# sematik.net
KiCad netlist of a schematic drawn in EAGLE
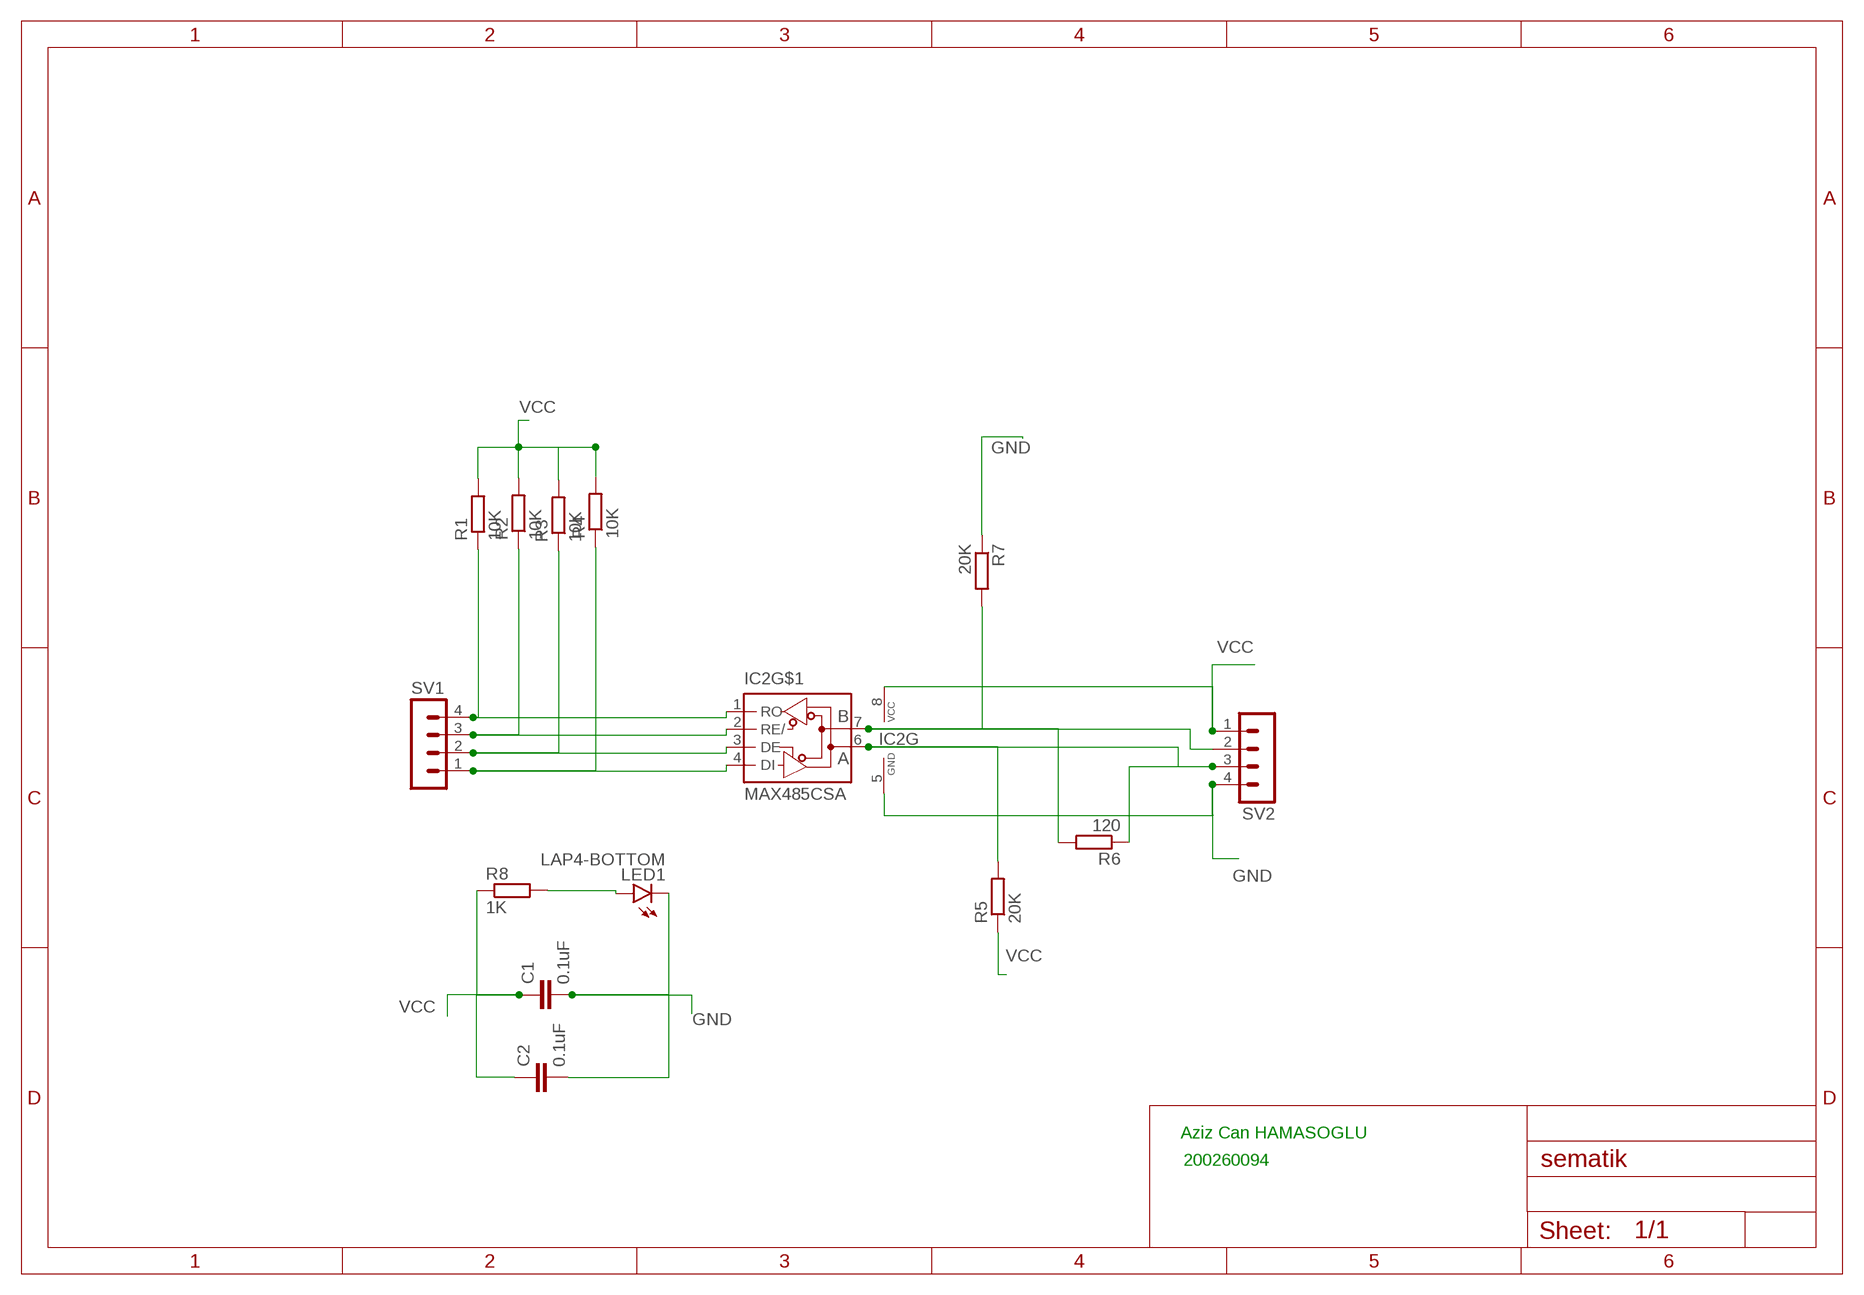
[diagram p0: schematic, sheet 1]

(export (version "E")
  (design (tool "Eeschema 10.0.6"))
  (components
    (comp (ref "C1")
      (value "0.1uF")
      (footprint "eagle-import:C0402K")
      (libsource (lib "eagle-import") (part "C-EUC0402K"))
    )
    (comp (ref "C2")
      (value "0.1uF")
      (footprint "eagle-import:C0402K")
      (libsource (lib "eagle-import") (part "C-EUC0402K"))
    )
    (comp (ref "IC2")
      (value "MAX485CSA")
      (footprint "eagle-import:SO08")
      (libsource (lib "eagle-import") (part "MAX485CSA"))
    )
    (comp (ref "LED1")
      (value "LAP4-BOTTOM")
      (footprint "eagle-import:P47F-BOTTOM")
      (libsource (lib "eagle-import") (part "P4-BOTTOMLA"))
    )
    (comp (ref "R1")
      (value "10K")
      (footprint "eagle-import:M1206")
      (libsource (lib "eagle-import") (part "R-EU_M1206"))
    )
    (comp (ref "R2")
      (value "10K")
      (footprint "eagle-import:M1206")
      (libsource (lib "eagle-import") (part "R-EU_M1206"))
    )
    (comp (ref "R3")
      (value "10K")
      (footprint "eagle-import:M1206")
      (libsource (lib "eagle-import") (part "R-EU_M1206"))
    )
    (comp (ref "R4")
      (value "10K")
      (footprint "eagle-import:M1206")
      (libsource (lib "eagle-import") (part "R-EU_M1206"))
    )
    (comp (ref "R5")
      (value "20K")
      (footprint "eagle-import:M1206")
      (libsource (lib "eagle-import") (part "R-EU_M1206"))
    )
    (comp (ref "R6")
      (value "120")
      (footprint "eagle-import:M1206")
      (libsource (lib "eagle-import") (part "R-EU_M1206"))
    )
    (comp (ref "R7")
      (value "20K")
      (footprint "eagle-import:M1206")
      (libsource (lib "eagle-import") (part "R-EU_M1206"))
    )
    (comp (ref "R8")
      (value "1K")
      (footprint "eagle-import:M1206")
      (libsource (lib "eagle-import") (part "R-EU_M1206"))
    )
    (comp (ref "SV1")
      (value "MA04-1")
      (footprint "eagle-import:MA04-1")
      (libsource (lib "eagle-import") (part "MA04-1"))
    )
    (comp (ref "SV2")
      (value "MA04-1")
      (footprint "eagle-import:MA04-1")
      (libsource (lib "eagle-import") (part "MA04-1"))
    )
  )
  (nets
    (net (code "1") (name "/GND") (class "Default")
      (node (ref "C1") (pin "2") (pinfunction "2_2") (pintype "passive"))
      (node (ref "C2") (pin "2") (pinfunction "2_2") (pintype "passive"))
      (node (ref "IC2") (pin "5") (pinfunction "GND_5") (pintype "power_in"))
      (node (ref "LED1") (pin "C") (pinfunction "C_C") (pintype "passive"))
      (node (ref "R7") (pin "1") (pinfunction "1_1") (pintype "passive"))
      (node (ref "SV2") (pin "4") (pinfunction "4_4") (pintype "passive"))
    )
    (net (code "2") (name "/VCC") (class "Default")
      (node (ref "C1") (pin "1") (pinfunction "1_1") (pintype "passive"))
      (node (ref "C2") (pin "1") (pinfunction "1_1") (pintype "passive"))
      (node (ref "IC2") (pin "8") (pinfunction "VCC_8") (pintype "power_in"))
      (node (ref "R1") (pin "2") (pinfunction "2_2") (pintype "passive"))
      (node (ref "R2") (pin "2") (pinfunction "2_2") (pintype "passive"))
      (node (ref "R3") (pin "2") (pinfunction "2_2") (pintype "passive"))
      (node (ref "R4") (pin "2") (pinfunction "2_2") (pintype "passive"))
      (node (ref "R5") (pin "1") (pinfunction "1_1") (pintype "passive"))
      (node (ref "R8") (pin "1") (pinfunction "1_1") (pintype "passive"))
      (node (ref "SV2") (pin "1") (pinfunction "1_1") (pintype "passive"))
    )
    (net (code "3") (name "Net-(IC2B-A)") (class "Default")
      (node (ref "IC2") (pin "6") (pinfunction "A_6") (pintype "passive"))
      (node (ref "R5") (pin "2") (pinfunction "2_2") (pintype "passive"))
      (node (ref "R6") (pin "1") (pinfunction "1_1") (pintype "passive"))
      (node (ref "SV2") (pin "3") (pinfunction "3_3") (pintype "passive"))
    )
    (net (code "4") (name "Net-(IC2B-B)") (class "Default")
      (node (ref "IC2") (pin "7") (pinfunction "B_7") (pintype "passive"))
      (node (ref "R6") (pin "2") (pinfunction "2_2") (pintype "passive"))
      (node (ref "R7") (pin "2") (pinfunction "2_2") (pintype "passive"))
      (node (ref "SV2") (pin "2") (pinfunction "2_2") (pintype "passive"))
    )
    (net (code "5") (name "Net-(IC2B-DE)") (class "Default")
      (node (ref "IC2") (pin "3") (pinfunction "DE_3") (pintype "input"))
      (node (ref "R3") (pin "1") (pinfunction "1_1") (pintype "passive"))
      (node (ref "SV1") (pin "2") (pinfunction "2_2") (pintype "passive"))
    )
    (net (code "6") (name "Net-(IC2B-DI)") (class "Default")
      (node (ref "IC2") (pin "4") (pinfunction "DI_4") (pintype "input"))
      (node (ref "R4") (pin "1") (pinfunction "1_1") (pintype "passive"))
      (node (ref "SV1") (pin "1") (pinfunction "1_1") (pintype "passive"))
    )
    (net (code "7") (name "Net-(IC2B-RE{slash})") (class "Default")
      (node (ref "IC2") (pin "2") (pinfunction "RE/_2") (pintype "input"))
      (node (ref "R2") (pin "1") (pinfunction "1_1") (pintype "passive"))
      (node (ref "SV1") (pin "3") (pinfunction "3_3") (pintype "passive"))
    )
    (net (code "8") (name "Net-(IC2B-RO)") (class "Default")
      (node (ref "IC2") (pin "1") (pinfunction "RO_1") (pintype "output"))
      (node (ref "R1") (pin "1") (pinfunction "1_1") (pintype "passive"))
      (node (ref "SV1") (pin "4") (pinfunction "4_4") (pintype "passive"))
    )
    (net (code "9") (name "Net-(LED1-PadA)") (class "Default")
      (node (ref "LED1") (pin "A") (pinfunction "A_A") (pintype "passive"))
      (node (ref "R8") (pin "2") (pinfunction "2_2") (pintype "passive"))
    )
  )
)
